# MCU.net
KiCad netlist of a schematic drawn in Altium Designer
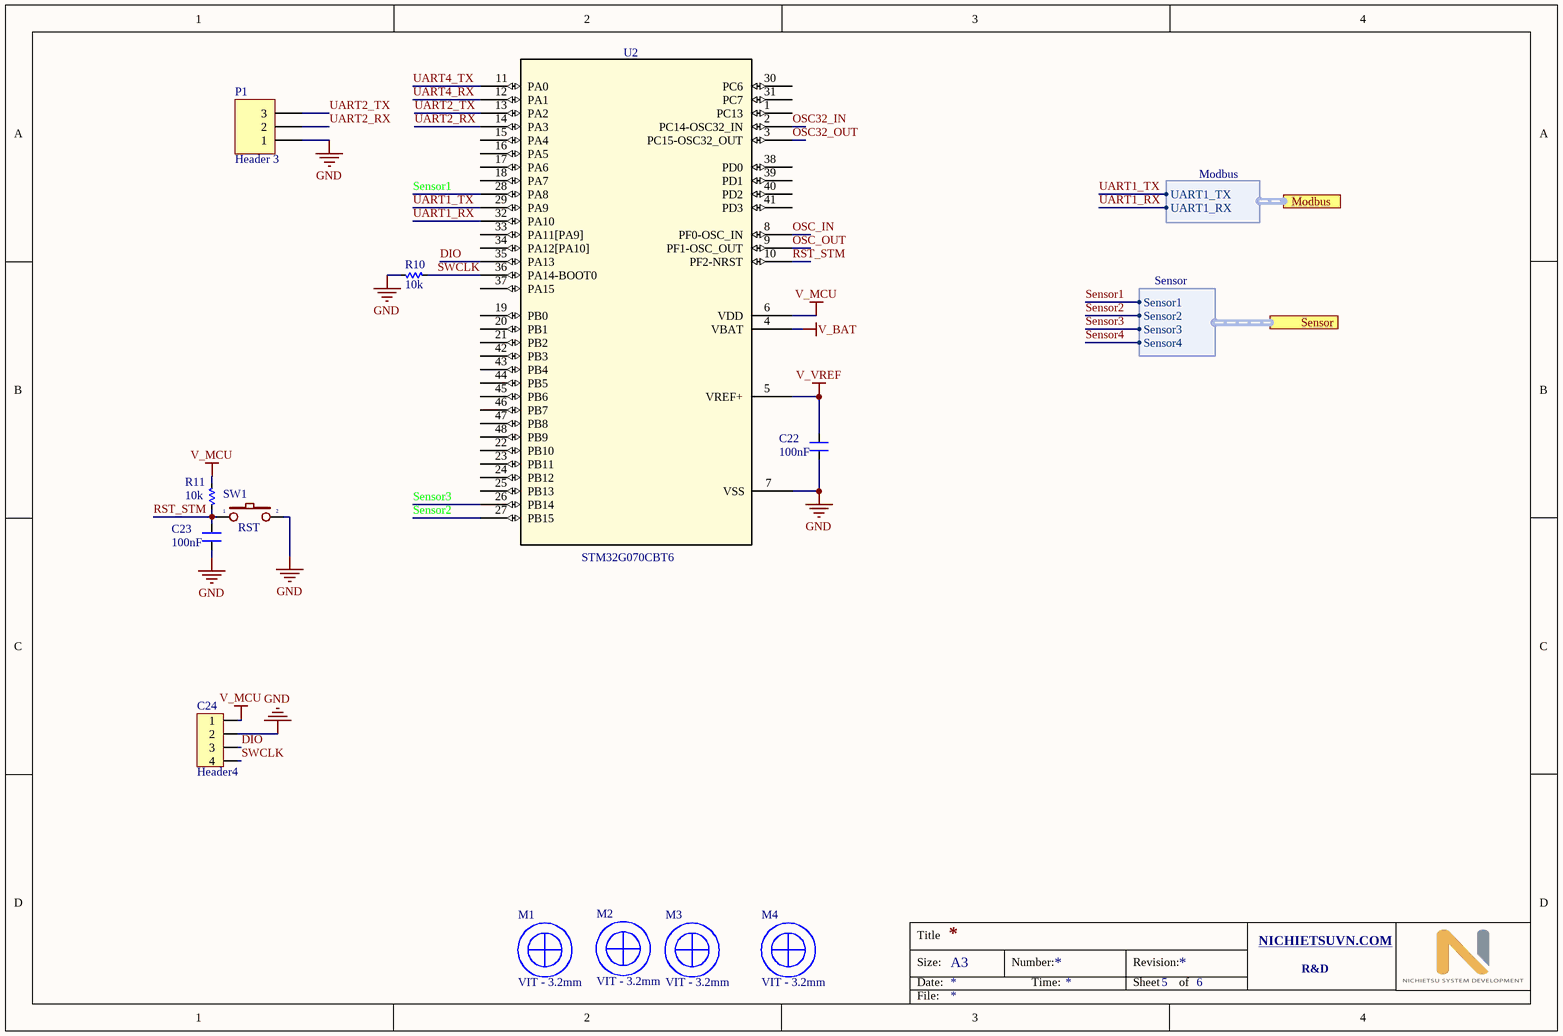
[diagram p0: MCU.SchDoc]

(export (version "E")
  (design (tool "Eeschema 10.0.6"))
  (components
    (comp (ref "C22") (value "100nF") (footprint "CN-SMD-0603") (libsource (lib "thu vien 3d") (part "CN")))
    (comp (ref "C23") (value "100nF") (footprint "CN-SMD-0603") (libsource (lib "thu vien 3d") (part "CN")))
    (comp (ref "C24")
      (value "Header4")
      (footprint "Header4")
      (description "Header IDC, 4 x 1 Pin Vertical 2.54mm Pitch (Non-Boxed, Male)")
      (fields
        (field (name "MANUFACTURER") "Würth Elektronik eiSos GmbH")
        (field (name "PARTNO") "613002143121")
        (field (name "CREATED BY") "Karrer Zheng")
      )
      (libsource (lib "thu vien 3d") (part "Header4"))
    )
    (comp (ref "M1")
      (value "VIT - 3.2mm")
      (footprint "VIT - 3.2MM_2")
      (libsource (lib "All Library") (part "VIT - 3.2mm_1"))
    )
    (comp (ref "M2")
      (value "VIT - 3.2mm")
      (footprint "VIT - 3.2MM_2")
      (libsource (lib "All Library") (part "VIT - 3.2mm_1"))
    )
    (comp (ref "M3")
      (value "VIT - 3.2mm")
      (footprint "VIT - 3.2MM_2")
      (libsource (lib "All Library") (part "VIT - 3.2mm_1"))
    )
    (comp (ref "M4")
      (value "VIT - 3.2mm")
      (footprint "VIT - 3.2MM_2")
      (libsource (lib "All Library") (part "VIT - 3.2mm_1"))
    )
    (comp (ref "P1")
      (value "Header 3")
      (footprint "Header 3")
      (description "Header, 3-Pin")
      (fields (field (name "PUBLISHER") "Altium Limited"))
      (libsource (lib "hphonglib") (part "Header 3"))
    )
    (comp (ref "R10")
      (value "10k")
      (footprint "RES-SMD-0603")
      (description "Resistor")
      (fields
        (field (name "MANUFACTURER") "Generic Components")
        (field (name "PUBLISHER") "Altium Hobart Technology Centre")
      )
      (libsource (lib "thu vien 3d") (part "Res-SMD"))
    )
    (comp (ref "R11")
      (value "10k")
      (footprint "RES-SMD-0603")
      (description "Resistor")
      (fields
        (field (name "MANUFACTURER") "Generic Components")
        (field (name "PUBLISHER") "Altium Hobart Technology Centre")
      )
      (libsource (lib "thu vien 3d") (part "Res-SMD"))
    )
    (comp (ref "SW1")
      (value "RST")
      (footprint "SW1-SMD")
      (description "Switch button 2 pin")
      (libsource (lib "thu vien 3d") (part "SW2"))
    )
    (comp (ref "U2")
      (value "STM32G070CBT6")
      (footprint "STM32G070CBT6")
      (description "No Description Available")
      (fields (field (name "COPYRIGHT") "Copyright (C) 2018 Accelerated Designs. All rights reserved"))
      (libsource (lib "Nichietsuvn") (part "STM32G070CBT6"))
    )
  )
  (nets
    (net (code "3") (name "/DIO") (class "Default")
      (node (ref "C24") (pin "3") (pinfunction "3_3") (pintype "passive"))
      (node (ref "U2") (pin "35") (pinfunction "PA13_35") (pintype "bidirectional"))
    )
    (net (code "4") (name "/OSC32_IN") (class "Default")
      (node (ref "U2") (pin "2") (pinfunction "PC14-OSC32_IN_2") (pintype "bidirectional"))
    )
    (net (code "5") (name "/OSC32_OUT") (class "Default")
      (node (ref "U2") (pin "3") (pinfunction "PC15-OSC32_OUT_3") (pintype "bidirectional"))
    )
    (net (code "6") (name "/OSC_IN") (class "Default")
      (node (ref "U2") (pin "8") (pinfunction "PF0-OSC_IN_8") (pintype "bidirectional"))
    )
    (net (code "7") (name "/OSC_OUT") (class "Default")
      (node (ref "U2") (pin "9") (pinfunction "PF1-OSC_OUT_9") (pintype "bidirectional"))
    )
    (net (code "8") (name "/RST_STM") (class "Default")
      (node (ref "C23") (pin "1") (pinfunction "1_1") (pintype "passive"))
      (node (ref "R11") (pin "2") (pinfunction "2_2") (pintype "passive"))
      (node (ref "SW1") (pin "1") (pinfunction "1_1") (pintype "passive"))
      (node (ref "U2") (pin "10") (pinfunction "PF2-NRST_10") (pintype "bidirectional"))
    )
    (net (code "9") (name "/SWCLK") (class "Default")
      (node (ref "C24") (pin "4") (pinfunction "4_4") (pintype "passive"))
      (node (ref "R10") (pin "1") (pinfunction "1_1") (pintype "passive"))
      (node (ref "U2") (pin "36") (pinfunction "PA14-BOOT0_36") (pintype "bidirectional"))
    )
    (net (code "10") (name "/Sensor1") (class "Default")
      (node (ref "U2") (pin "28") (pinfunction "PA8_28") (pintype "bidirectional"))
    )
    (net (code "11") (name "/Sensor2") (class "Default")
      (node (ref "U2") (pin "27") (pinfunction "PB15_27") (pintype "bidirectional"))
    )
    (net (code "12") (name "/Sensor3") (class "Default")
      (node (ref "U2") (pin "26") (pinfunction "PB14_26") (pintype "bidirectional"))
    )
    (net (code "14") (name "/UART1_RX") (class "Default")
      (node (ref "U2") (pin "32") (pinfunction "PA10_32") (pintype "bidirectional"))
    )
    (net (code "15") (name "/UART1_TX") (class "Default")
      (node (ref "U2") (pin "29") (pinfunction "PA9_29") (pintype "bidirectional"))
    )
    (net (code "16") (name "/UART2_RX") (class "Default")
      (node (ref "P1") (pin "2") (pinfunction "2_2") (pintype "passive"))
      (node (ref "U2") (pin "14") (pinfunction "PA3_14") (pintype "bidirectional"))
    )
    (net (code "17") (name "/UART2_TX") (class "Default")
      (node (ref "P1") (pin "3") (pinfunction "3_3") (pintype "passive"))
      (node (ref "U2") (pin "13") (pinfunction "PA2_13") (pintype "bidirectional"))
    )
    (net (code "18") (name "/UART4_RX") (class "Default")
      (node (ref "U2") (pin "12") (pinfunction "PA1_12") (pintype "bidirectional"))
    )
    (net (code "19") (name "/UART4_TX") (class "Default")
      (node (ref "U2") (pin "11") (pinfunction "PA0_11") (pintype "bidirectional"))
    )
    (net (code "22") (name "GND") (class "Default")
      (node (ref "C22") (pin "2") (pinfunction "2_2") (pintype "passive"))
      (node (ref "C23") (pin "2") (pinfunction "2_2") (pintype "passive"))
      (node (ref "C24") (pin "2") (pinfunction "2_2") (pintype "passive"))
      (node (ref "P1") (pin "1") (pinfunction "1_1") (pintype "passive"))
      (node (ref "R10") (pin "2") (pinfunction "2_2") (pintype "passive"))
      (node (ref "SW1") (pin "2") (pinfunction "2_2") (pintype "passive"))
      (node (ref "U2") (pin "7") (pinfunction "VSS_7") (pintype "power_in"))
    )
    (net (code "23") (name "V_BAT") (class "Default")
      (node (ref "U2") (pin "4") (pinfunction "VBAT_4") (pintype "power_in"))
    )
    (net (code "24") (name "V_MCU") (class "Default")
      (node (ref "C24") (pin "1") (pinfunction "1_1") (pintype "passive"))
      (node (ref "R11") (pin "1") (pinfunction "1_1") (pintype "passive"))
      (node (ref "U2") (pin "6") (pinfunction "VDD_6") (pintype "power_in"))
    )
    (net (code "25") (name "V_VREF") (class "Default")
      (node (ref "C22") (pin "1") (pinfunction "1_1") (pintype "passive"))
      (node (ref "U2") (pin "5") (pinfunction "VREF+_5") (pintype "power_in"))
    )
    (net (code "26") (name "unconnected-(U2-PA4-Pad15)") (class "Default")
      (node (ref "U2") (pin "15") (pinfunction "PA4_15") (pintype "bidirectional"))
    )
    (net (code "27") (name "unconnected-(U2-PA5-Pad16)") (class "Default")
      (node (ref "U2") (pin "16") (pinfunction "PA5_16") (pintype "bidirectional"))
    )
    (net (code "28") (name "unconnected-(U2-PA6-Pad17)") (class "Default")
      (node (ref "U2") (pin "17") (pinfunction "PA6_17") (pintype "bidirectional"))
    )
    (net (code "29") (name "unconnected-(U2-PA7-Pad18)") (class "Default")
      (node (ref "U2") (pin "18") (pinfunction "PA7_18") (pintype "bidirectional"))
    )
    (net (code "30") (name "unconnected-(U2-PA11[PA9]-Pad33)") (class "Default")
      (node (ref "U2") (pin "33") (pinfunction "PA11[PA9]_33") (pintype "bidirectional"))
    )
    (net (code "31") (name "unconnected-(U2-PA12[PA10]-Pad34)") (class "Default")
      (node (ref "U2") (pin "34") (pinfunction "PA12[PA10]_34") (pintype "bidirectional"))
    )
    (net (code "32") (name "unconnected-(U2-PA15-Pad37)") (class "Default")
      (node (ref "U2") (pin "37") (pinfunction "PA15_37") (pintype "bidirectional"))
    )
    (net (code "33") (name "unconnected-(U2-PB0-Pad19)") (class "Default")
      (node (ref "U2") (pin "19") (pinfunction "PB0_19") (pintype "bidirectional"))
    )
    (net (code "34") (name "unconnected-(U2-PB1-Pad20)") (class "Default")
      (node (ref "U2") (pin "20") (pinfunction "PB1_20") (pintype "bidirectional"))
    )
    (net (code "35") (name "unconnected-(U2-PB2-Pad21)") (class "Default")
      (node (ref "U2") (pin "21") (pinfunction "PB2_21") (pintype "bidirectional"))
    )
    (net (code "36") (name "unconnected-(U2-PB3-Pad42)") (class "Default")
      (node (ref "U2") (pin "42") (pinfunction "PB3_42") (pintype "bidirectional"))
    )
    (net (code "37") (name "unconnected-(U2-PB4-Pad43)") (class "Default")
      (node (ref "U2") (pin "43") (pinfunction "PB4_43") (pintype "bidirectional"))
    )
    (net (code "38") (name "unconnected-(U2-PB5-Pad44)") (class "Default")
      (node (ref "U2") (pin "44") (pinfunction "PB5_44") (pintype "bidirectional"))
    )
    (net (code "39") (name "unconnected-(U2-PB6-Pad45)") (class "Default")
      (node (ref "U2") (pin "45") (pinfunction "PB6_45") (pintype "bidirectional"))
    )
    (net (code "40") (name "unconnected-(U2-PB7-Pad46)") (class "Default")
      (node (ref "U2") (pin "46") (pinfunction "PB7_46") (pintype "bidirectional"))
    )
    (net (code "41") (name "unconnected-(U2-PB8-Pad47)") (class "Default")
      (node (ref "U2") (pin "47") (pinfunction "PB8_47") (pintype "bidirectional"))
    )
    (net (code "42") (name "unconnected-(U2-PB9-Pad48)") (class "Default")
      (node (ref "U2") (pin "48") (pinfunction "PB9_48") (pintype "bidirectional"))
    )
    (net (code "43") (name "unconnected-(U2-PB10-Pad22)") (class "Default")
      (node (ref "U2") (pin "22") (pinfunction "PB10_22") (pintype "bidirectional"))
    )
    (net (code "44") (name "unconnected-(U2-PB11-Pad23)") (class "Default")
      (node (ref "U2") (pin "23") (pinfunction "PB11_23") (pintype "bidirectional"))
    )
    (net (code "45") (name "unconnected-(U2-PB12-Pad24)") (class "Default")
      (node (ref "U2") (pin "24") (pinfunction "PB12_24") (pintype "bidirectional"))
    )
    (net (code "46") (name "unconnected-(U2-PB13-Pad25)") (class "Default")
      (node (ref "U2") (pin "25") (pinfunction "PB13_25") (pintype "bidirectional"))
    )
    (net (code "47") (name "unconnected-(U2-PC6-Pad30)") (class "Default")
      (node (ref "U2") (pin "30") (pinfunction "PC6_30") (pintype "bidirectional"))
    )
    (net (code "48") (name "unconnected-(U2-PC7-Pad31)") (class "Default")
      (node (ref "U2") (pin "31") (pinfunction "PC7_31") (pintype "bidirectional"))
    )
    (net (code "49") (name "unconnected-(U2-PC13-Pad1)") (class "Default")
      (node (ref "U2") (pin "1") (pinfunction "PC13_1") (pintype "bidirectional"))
    )
    (net (code "50") (name "unconnected-(U2-PD0-Pad38)") (class "Default")
      (node (ref "U2") (pin "38") (pinfunction "PD0_38") (pintype "bidirectional"))
    )
    (net (code "51") (name "unconnected-(U2-PD1-Pad39)") (class "Default")
      (node (ref "U2") (pin "39") (pinfunction "PD1_39") (pintype "bidirectional"))
    )
    (net (code "52") (name "unconnected-(U2-PD2-Pad40)") (class "Default")
      (node (ref "U2") (pin "40") (pinfunction "PD2_40") (pintype "bidirectional"))
    )
    (net (code "53") (name "unconnected-(U2-PD3-Pad41)") (class "Default")
      (node (ref "U2") (pin "41") (pinfunction "PD3_41") (pintype "bidirectional"))
    )
  )
)
